# V-00735-01.net
KiCad netlist of a schematic drawn in EAGLE
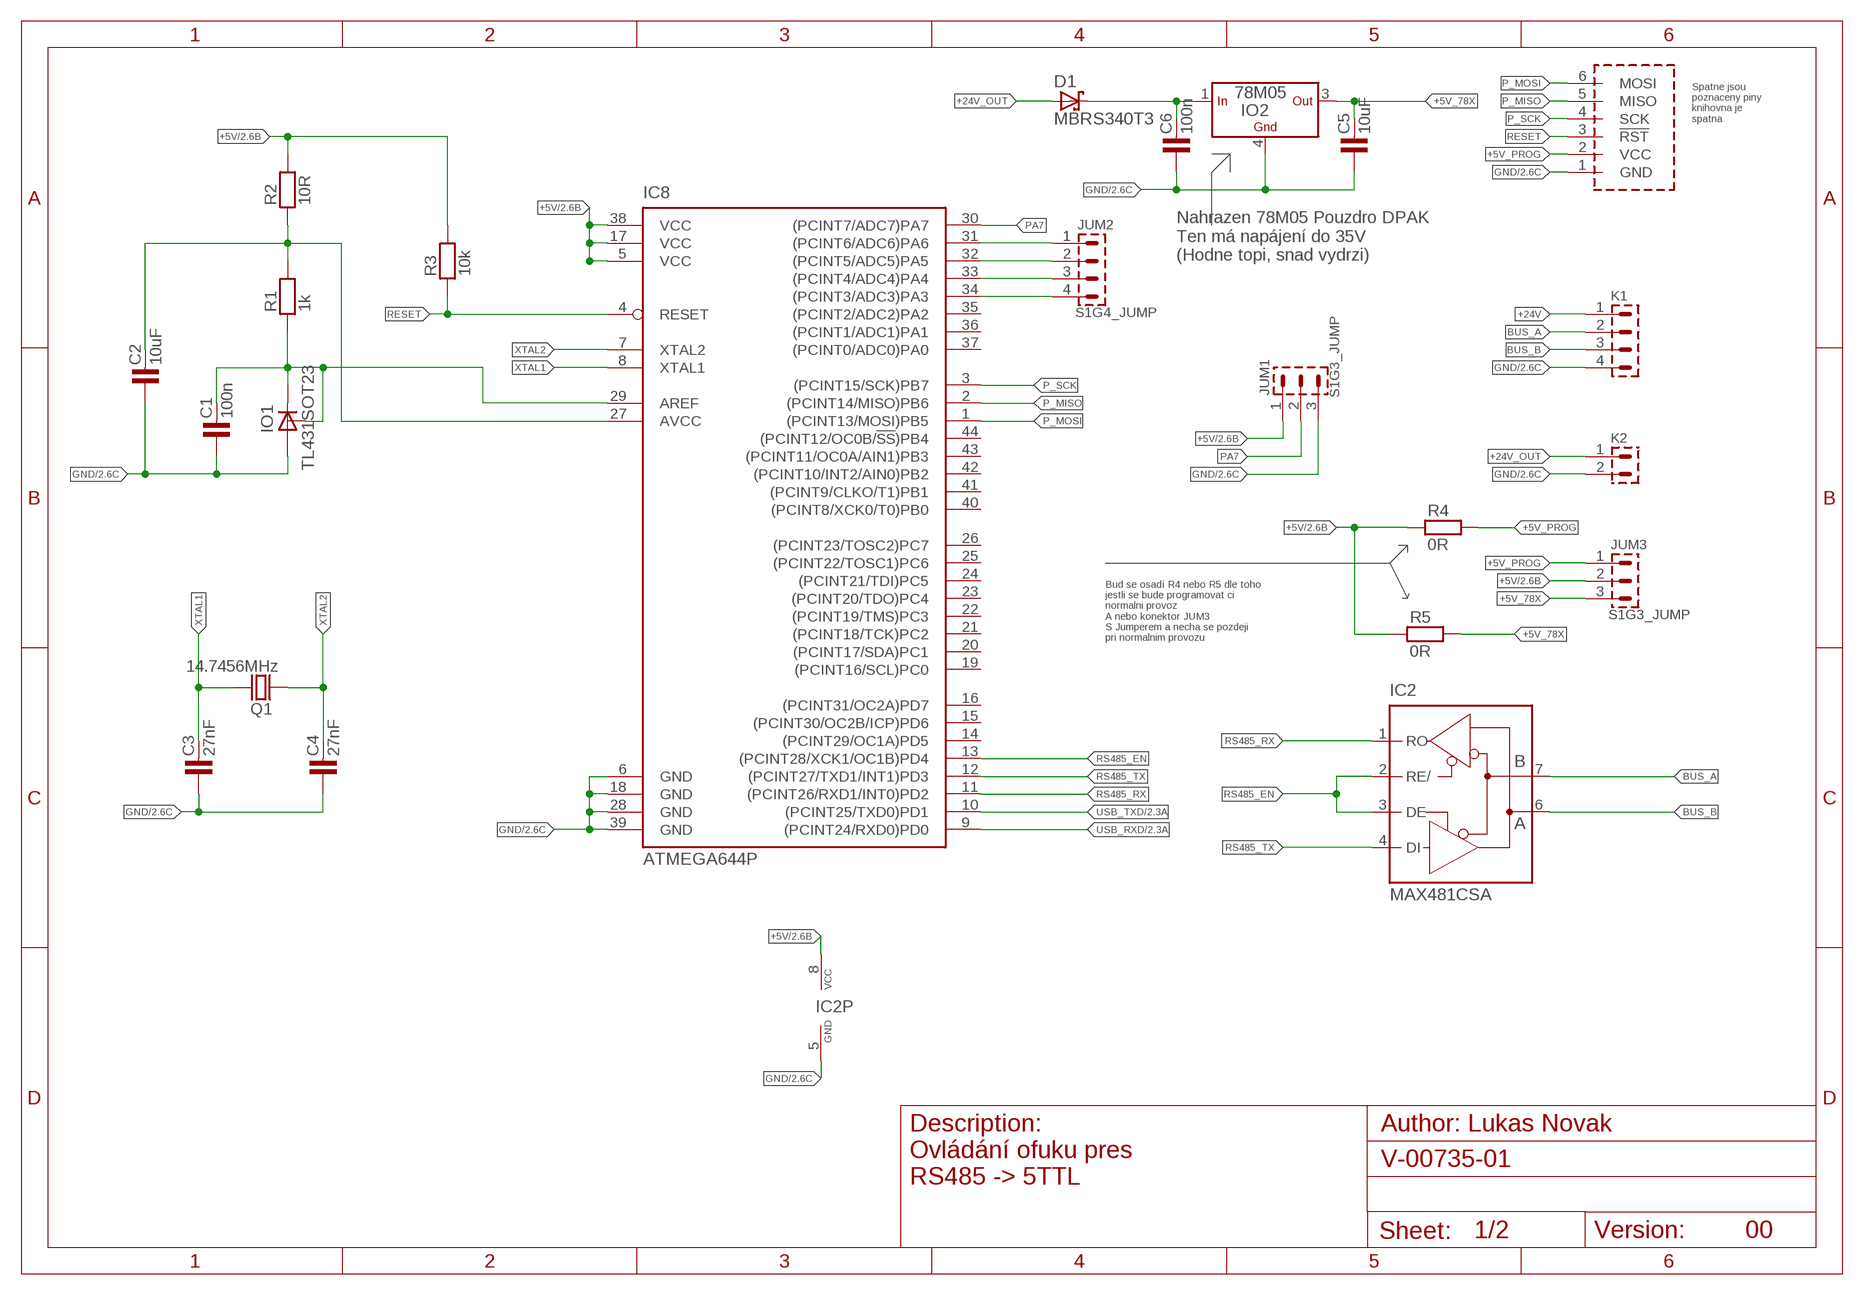
[diagram p0: schematic, sheet 1]
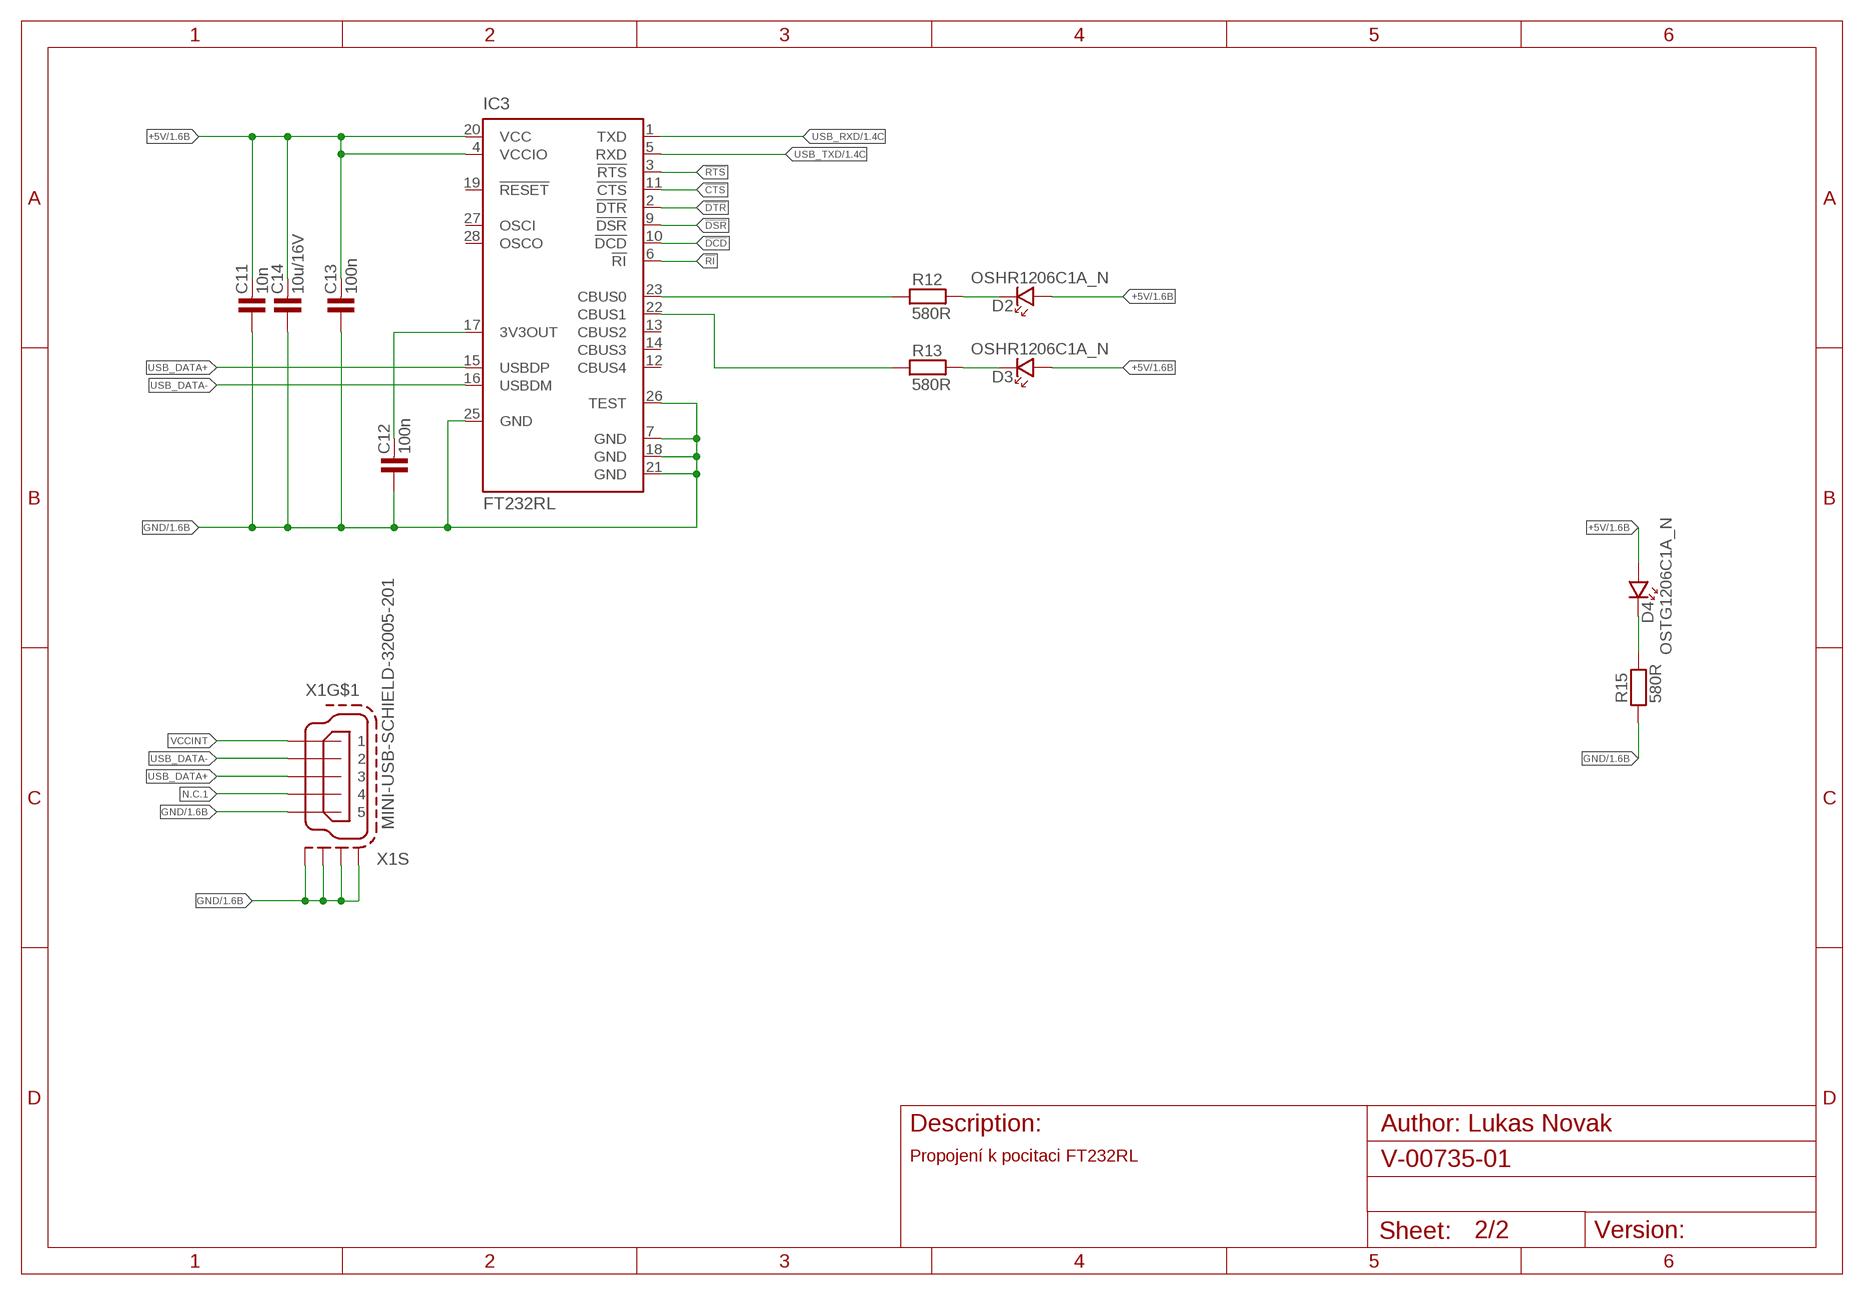
[diagram p1: schematic, sheet 2]

(export (version "E")
  (design (tool "Eeschema 10.0.6"))
  (components
    (comp (ref "C11")
      (value "10n")
      (footprint "eagle-import:1206")
      (libsource (lib "eagle-import") (part "C-KER_1206"))
    )
    (comp (ref "C12")
      (value "100n")
      (footprint "eagle-import:1206")
      (libsource (lib "eagle-import") (part "C-KER_1206"))
    )
    (comp (ref "C13")
      (value "100n")
      (footprint "eagle-import:1206")
      (libsource (lib "eagle-import") (part "C-KER_1206"))
    )
    (comp (ref "C14")
      (value "10u/16V")
      (footprint "eagle-import:1206")
      (libsource (lib "eagle-import") (part "C-KER_1206"))
    )
    (comp (ref "D2")
      (value "OSHR1206C1A_N")
      (footprint "eagle-import:P1206")
      (libsource (lib "eagle-import") (part "LED_1206"))
    )
    (comp (ref "D3")
      (value "OSHR1206C1A_N")
      (footprint "eagle-import:P1206")
      (libsource (lib "eagle-import") (part "LED_1206"))
    )
    (comp (ref "D4")
      (value "OSTG1206C1A_N")
      (footprint "eagle-import:P1206")
      (libsource (lib "eagle-import") (part "LED_1206"))
    )
    (comp (ref "IC3")
      (value "FT232RL")
      (footprint "eagle-import:SSOP28")
      (libsource (lib "eagle-import") (part "FT232RL"))
    )
    (comp (ref "R12")
      (value "580R")
      (footprint "eagle-import:1206")
      (libsource (lib "eagle-import") (part "R_1206"))
    )
    (comp (ref "R13")
      (value "580R")
      (footprint "eagle-import:1206")
      (libsource (lib "eagle-import") (part "R_1206"))
    )
    (comp (ref "R15")
      (value "580R")
      (footprint "eagle-import:1206")
      (libsource (lib "eagle-import") (part "R_1206"))
    )
    (comp (ref "X1")
      (value "MINI-USB-SCHIELD-32005-201")
      (footprint "eagle-import:32005-201")
      (libsource (lib "eagle-import") (part "MINI-USB-SCHIELD-32005-201"))
    )
    (comp (ref "C1")
      (value "100n")
      (footprint "eagle-import:1206")
      (libsource (lib "eagle-import") (part "C-KER_1206"))
    )
    (comp (ref "C2")
      (value "10uF")
      (footprint "eagle-import:1206")
      (libsource (lib "eagle-import") (part "C-KER_1206"))
    )
    (comp (ref "C3")
      (value "27nF")
      (footprint "eagle-import:0805")
      (libsource (lib "eagle-import") (part "C-KER_0805"))
    )
    (comp (ref "C4")
      (value "27nF")
      (footprint "eagle-import:0805")
      (libsource (lib "eagle-import") (part "C-KER_0805"))
    )
    (comp (ref "C5")
      (value "10uF")
      (footprint "eagle-import:1206")
      (libsource (lib "eagle-import") (part "C-KER_1206"))
    )
    (comp (ref "C6")
      (value "100n")
      (footprint "eagle-import:1206")
      (libsource (lib "eagle-import") (part "C-KER_1206"))
    )
    (comp (ref "D1")
      (value "MBRS340T3")
      (footprint "eagle-import:SMC")
      (libsource (lib "eagle-import") (part "MBRS30T34"))
    )
    (comp (ref "IC2")
      (value "MAX481CSA")
      (footprint "eagle-import:SO08")
      (fields (field (name "MF") "MAXIM"))
      (libsource (lib "eagle-import") (part "MAX481CSA"))
    )
    (comp (ref "IC8")
      (value "ATMEGA644P")
      (footprint "eagle-import:TQFP44")
      (libsource (lib "eagle-import") (part "ATMEGA644P"))
    )
    (comp (ref "IO1")
      (value "TL431SOT23")
      (footprint "eagle-import:SOT23")
      (fields (field (name "MPN") "TL431BFDT"))
      (libsource (lib "eagle-import") (part "TL431SOT23"))
    )
    (comp (ref "IO2")
      (value "78M05")
      (footprint "eagle-import:DPAK")
      (libsource (lib "eagle-import") (part "LF_CDT"))
    )
    (comp (ref "JUM1")
      (value "S1G3_JUMP")
      (footprint "eagle-import:S1G3_JUM")
      (libsource (lib "eagle-import") (part "S1G3_JUMP"))
    )
    (comp (ref "JUM2")
      (value "S1G4_JUMP")
      (footprint "eagle-import:S1G4_JUM")
      (libsource (lib "eagle-import") (part "S1G4_JUMP"))
    )
    (comp (ref "JUM3")
      (value "S1G3_JUMP")
      (footprint "eagle-import:S1G3_JUM")
      (libsource (lib "eagle-import") (part "S1G3_JUMP"))
    )
    (comp (ref "K1")
      (value "PSH02-04P")
      (footprint "eagle-import:PSH02-04P")
      (libsource (lib "eagle-import") (part "PSH02-04P"))
    )
    (comp (ref "K2")
      (value "PSH02-02P")
      (footprint "eagle-import:PSH02-02P")
      (libsource (lib "eagle-import") (part "PSH02-02P"))
    )
    (comp (ref "Q1")
      (value "14.7456MHz")
      (footprint "eagle-import:HC-49U")
      (libsource (lib "eagle-import") (part "Q_HC-49U"))
    )
    (comp (ref "R1")
      (value "1k")
      (footprint "eagle-import:1206")
      (libsource (lib "eagle-import") (part "R_1206"))
    )
    (comp (ref "R2")
      (value "10R")
      (footprint "eagle-import:1206")
      (libsource (lib "eagle-import") (part "R_1206"))
    )
    (comp (ref "R3")
      (value "10k")
      (footprint "eagle-import:1206")
      (libsource (lib "eagle-import") (part "R_1206"))
    )
    (comp (ref "R4")
      (value "0R")
      (footprint "eagle-import:1206")
      (libsource (lib "eagle-import") (part "R_1206"))
    )
    (comp (ref "R5")
      (value "0R")
      (footprint "eagle-import:1206")
      (libsource (lib "eagle-import") (part "R_1206"))
    )
    (comp (ref "U$1")
      (value "AVR_PROG_SPI")
      (footprint "eagle-import:PSH02-06P")
      (libsource (lib "eagle-import") (part "AVR_PROG_SPI"))
    )
  )
  (nets
    (net (code "1") (name "+5V") (class "Default")
      (node (ref "C11") (pin "2") (pinfunction "2_2") (pintype "passive"))
      (node (ref "C13") (pin "2") (pinfunction "2_2") (pintype "passive"))
      (node (ref "C14") (pin "2") (pinfunction "2_2") (pintype "passive"))
      (node (ref "D2") (pin "A") (pinfunction "A_A") (pintype "passive"))
      (node (ref "D3") (pin "A") (pinfunction "A_A") (pintype "passive"))
      (node (ref "D4") (pin "A") (pinfunction "A_A") (pintype "passive"))
      (node (ref "IC2") (pin "8") (pinfunction "VCC_8") (pintype "power_in"))
      (node (ref "IC3") (pin "20") (pinfunction "VCC_20") (pintype "power_in"))
      (node (ref "IC3") (pin "4") (pinfunction "VCCIO_4") (pintype "power_in"))
      (node (ref "IC8") (pin "17") (pinfunction "VCC_17") (pintype "power_in"))
      (node (ref "IC8") (pin "38") (pinfunction "VCC_38") (pintype "power_in"))
      (node (ref "IC8") (pin "5") (pinfunction "VCC_5") (pintype "power_in"))
      (node (ref "JUM1") (pin "1") (pinfunction "1_1") (pintype "passive"))
      (node (ref "JUM3") (pin "2") (pinfunction "2_2") (pintype "passive"))
      (node (ref "R2") (pin "2") (pinfunction "2_2") (pintype "passive"))
      (node (ref "R3") (pin "2") (pinfunction "2_2") (pintype "passive"))
      (node (ref "R4") (pin "1") (pinfunction "1_1") (pintype "passive"))
      (node (ref "R5") (pin "1") (pinfunction "1_1") (pintype "passive"))
    )
    (net (code "2") (name "+5V_78X") (class "Default")
      (node (ref "C5") (pin "2") (pinfunction "2_2") (pintype "passive"))
      (node (ref "IO2") (pin "3") (pinfunction "OUT_3") (pintype "passive"))
      (node (ref "JUM3") (pin "3") (pinfunction "3_3") (pintype "passive"))
      (node (ref "R5") (pin "2") (pinfunction "2_2") (pintype "passive"))
    )
    (net (code "3") (name "+5V_PROG") (class "Default")
      (node (ref "JUM3") (pin "1") (pinfunction "1_1") (pintype "passive"))
      (node (ref "R4") (pin "2") (pinfunction "2_2") (pintype "passive"))
      (node (ref "U$1") (pin "2") (pinfunction "VCC_2") (pintype "bidirectional"))
    )
    (net (code "4") (name "+24V") (class "Default")
      (node (ref "C6") (pin "2") (pinfunction "2_2") (pintype "passive"))
      (node (ref "D1") (pin "C") (pinfunction "C_C") (pintype "passive"))
      (node (ref "IO2") (pin "1") (pinfunction "IN_1") (pintype "passive"))
      (node (ref "K1") (pin "1") (pinfunction "1_1") (pintype "passive"))
    )
    (net (code "5") (name "+24V_OUT") (class "Default")
      (node (ref "D1") (pin "A") (pinfunction "A_A") (pintype "passive"))
      (node (ref "K2") (pin "1") (pinfunction "1_1") (pintype "passive"))
    )
    (net (code "6") (name "BUS_A") (class "Default")
      (node (ref "IC2") (pin "7") (pinfunction "B_7") (pintype "passive"))
      (node (ref "K1") (pin "2") (pinfunction "2_2") (pintype "passive"))
    )
    (net (code "7") (name "BUS_B") (class "Default")
      (node (ref "IC2") (pin "6") (pinfunction "A_6") (pintype "passive"))
      (node (ref "K1") (pin "3") (pinfunction "3_3") (pintype "passive"))
    )
    (net (code "8") (name "GND") (class "Default")
      (node (ref "C1") (pin "1") (pinfunction "1_1") (pintype "passive"))
      (node (ref "C11") (pin "1") (pinfunction "1_1") (pintype "passive"))
      (node (ref "C12") (pin "1") (pinfunction "1_1") (pintype "passive"))
      (node (ref "C13") (pin "1") (pinfunction "1_1") (pintype "passive"))
      (node (ref "C14") (pin "1") (pinfunction "1_1") (pintype "passive"))
      (node (ref "C2") (pin "1") (pinfunction "1_1") (pintype "passive"))
      (node (ref "C3") (pin "1") (pinfunction "1_1") (pintype "passive"))
      (node (ref "C4") (pin "1") (pinfunction "1_1") (pintype "passive"))
      (node (ref "C5") (pin "1") (pinfunction "1_1") (pintype "passive"))
      (node (ref "C6") (pin "1") (pinfunction "1_1") (pintype "passive"))
      (node (ref "IC2") (pin "5") (pinfunction "GND_5") (pintype "power_in"))
      (node (ref "IC3") (pin "18") (pinfunction "GND_18") (pintype "power_in"))
      (node (ref "IC3") (pin "21") (pinfunction "GND_21") (pintype "power_in"))
      (node (ref "IC3") (pin "25") (pinfunction "GND_25") (pintype "power_in"))
      (node (ref "IC3") (pin "26") (pinfunction "TEST_26") (pintype "input"))
      (node (ref "IC3") (pin "7") (pinfunction "GND_7") (pintype "power_in"))
      (node (ref "IC8") (pin "18") (pinfunction "GND_18") (pintype "power_in"))
      (node (ref "IC8") (pin "28") (pinfunction "GND_28") (pintype "power_in"))
      (node (ref "IC8") (pin "39") (pinfunction "GND_39") (pintype "power_in"))
      (node (ref "IC8") (pin "6") (pinfunction "GND_6") (pintype "power_in"))
      (node (ref "IO1") (pin "3") (pinfunction "A_3") (pintype "bidirectional"))
      (node (ref "IO2") (pin "4") (pinfunction "GND_4") (pintype "passive"))
      (node (ref "JUM1") (pin "3") (pinfunction "3_3") (pintype "passive"))
      (node (ref "K1") (pin "4") (pinfunction "4_4") (pintype "passive"))
      (node (ref "K2") (pin "2") (pinfunction "2_2") (pintype "passive"))
      (node (ref "R15") (pin "1") (pinfunction "1_1") (pintype "passive"))
      (node (ref "U$1") (pin "1") (pinfunction "GND_1") (pintype "bidirectional"))
      (node (ref "X1") (pin "5") (pinfunction "5_5") (pintype "passive"))
      (node (ref "X1") (pin "M1") (pinfunction "S1_M1") (pintype "passive"))
      (node (ref "X1") (pin "M2") (pinfunction "S2_M2") (pintype "passive"))
      (node (ref "X1") (pin "M3") (pinfunction "S3_M3") (pintype "passive"))
      (node (ref "X1") (pin "M4") (pinfunction "S4_M4") (pintype "passive"))
    )
    (net (code "9") (name "N.C.1") (class "Default")
      (node (ref "X1") (pin "4") (pinfunction "4_4") (pintype "passive"))
    )
    (net (code "10") (name "Net-(D2-PadK)") (class "Default")
      (node (ref "D2") (pin "K") (pinfunction "K_K") (pintype "passive"))
      (node (ref "R12") (pin "2") (pinfunction "2_2") (pintype "passive"))
    )
    (net (code "11") (name "Net-(D3-PadK)") (class "Default")
      (node (ref "D3") (pin "K") (pinfunction "K_K") (pintype "passive"))
      (node (ref "R13") (pin "2") (pinfunction "2_2") (pintype "passive"))
    )
    (net (code "12") (name "Net-(D4-PadK)") (class "Default")
      (node (ref "D4") (pin "K") (pinfunction "K_K") (pintype "passive"))
      (node (ref "R15") (pin "2") (pinfunction "2_2") (pintype "passive"))
    )
    (net (code "13") (name "Net-(IC3-3V3OUT)") (class "Default")
      (node (ref "C12") (pin "2") (pinfunction "2_2") (pintype "passive"))
      (node (ref "IC3") (pin "17") (pinfunction "3V3OUT_17") (pintype "output"))
    )
    (net (code "14") (name "Net-(IC3-CBUS0)") (class "Default")
      (node (ref "IC3") (pin "23") (pinfunction "CBUS0_23") (pintype "bidirectional"))
      (node (ref "R12") (pin "1") (pinfunction "1_1") (pintype "passive"))
    )
    (net (code "15") (name "Net-(IC3-CBUS1)") (class "Default")
      (node (ref "IC3") (pin "22") (pinfunction "CBUS1_22") (pintype "bidirectional"))
      (node (ref "R13") (pin "1") (pinfunction "1_1") (pintype "passive"))
    )
    (net (code "16") (name "Net-(IC8-(PCINT3{slash}ADC3)PA3)") (class "Default")
      (node (ref "IC8") (pin "34") (pinfunction "(PCINT3/ADC3)PA3_34") (pintype "bidirectional"))
      (node (ref "JUM2") (pin "4") (pinfunction "4_4") (pintype "passive"))
    )
    (net (code "17") (name "Net-(IC8-(PCINT4{slash}ADC4)PA4)") (class "Default")
      (node (ref "IC8") (pin "33") (pinfunction "(PCINT4/ADC4)PA4_33") (pintype "bidirectional"))
      (node (ref "JUM2") (pin "3") (pinfunction "3_3") (pintype "passive"))
    )
    (net (code "18") (name "Net-(IC8-(PCINT5{slash}ADC5)PA5)") (class "Default")
      (node (ref "IC8") (pin "32") (pinfunction "(PCINT5/ADC5)PA5_32") (pintype "bidirectional"))
      (node (ref "JUM2") (pin "2") (pinfunction "2_2") (pintype "passive"))
    )
    (net (code "19") (name "Net-(IC8-(PCINT6{slash}ADC6)PA6)") (class "Default")
      (node (ref "IC8") (pin "31") (pinfunction "(PCINT6/ADC6)PA6_31") (pintype "bidirectional"))
      (node (ref "JUM2") (pin "1") (pinfunction "1_1") (pintype "passive"))
    )
    (net (code "20") (name "Net-(IC8-AREF)") (class "Default")
      (node (ref "C1") (pin "2") (pinfunction "2_2") (pintype "passive"))
      (node (ref "IC8") (pin "29") (pinfunction "AREF_29") (pintype "passive"))
      (node (ref "IO1") (pin "1") (pinfunction "C_1") (pintype "bidirectional"))
      (node (ref "IO1") (pin "2") (pinfunction "R_2") (pintype "bidirectional"))
      (node (ref "R1") (pin "1") (pinfunction "1_1") (pintype "passive"))
    )
    (net (code "21") (name "Net-(IC8-AVCC)") (class "Default")
      (node (ref "C2") (pin "2") (pinfunction "2_2") (pintype "passive"))
      (node (ref "IC8") (pin "27") (pinfunction "AVCC_27") (pintype "power_in"))
      (node (ref "R1") (pin "2") (pinfunction "2_2") (pintype "passive"))
      (node (ref "R2") (pin "1") (pinfunction "1_1") (pintype "passive"))
    )
    (net (code "22") (name "PA7") (class "Default")
      (node (ref "IC8") (pin "30") (pinfunction "(PCINT7/ADC7)PA7_30") (pintype "bidirectional"))
      (node (ref "JUM1") (pin "2") (pinfunction "2_2") (pintype "passive"))
    )
    (net (code "23") (name "P_MISO") (class "Default")
      (node (ref "IC8") (pin "2") (pinfunction "(PCINT14/MISO)PB6_2") (pintype "bidirectional"))
      (node (ref "U$1") (pin "5") (pinfunction "MISO_5") (pintype "bidirectional"))
    )
    (net (code "24") (name "P_MOSI") (class "Default")
      (node (ref "IC8") (pin "1") (pinfunction "(PCINT13/MOSI)PB5_1") (pintype "bidirectional"))
      (node (ref "U$1") (pin "6") (pinfunction "MOSI_6") (pintype "bidirectional"))
    )
    (net (code "25") (name "P_SCK") (class "Default")
      (node (ref "IC8") (pin "3") (pinfunction "(PCINT15/SCK)PB7_3") (pintype "bidirectional"))
      (node (ref "U$1") (pin "4") (pinfunction "SCK_4") (pintype "bidirectional"))
    )
    (net (code "26") (name "RESET") (class "Default")
      (node (ref "IC8") (pin "4") (pinfunction "RESET_4") (pintype "input"))
      (node (ref "R3") (pin "1") (pinfunction "1_1") (pintype "passive"))
      (node (ref "U$1") (pin "3") (pinfunction "~{RST}_3") (pintype "bidirectional"))
    )
    (net (code "27") (name "RS485_EN") (class "Default")
      (node (ref "IC2") (pin "2") (pinfunction "RE/_2") (pintype "input"))
      (node (ref "IC2") (pin "3") (pinfunction "DE_3") (pintype "input"))
      (node (ref "IC8") (pin "13") (pinfunction "(PCINT28/XCK1/OC1B)PD4_13") (pintype "bidirectional"))
    )
    (net (code "28") (name "RS485_RX") (class "Default")
      (node (ref "IC2") (pin "1") (pinfunction "RO_1") (pintype "output"))
      (node (ref "IC8") (pin "11") (pinfunction "(PCINT26/RXD1/INT0)PD2_11") (pintype "bidirectional"))
    )
    (net (code "29") (name "RS485_TX") (class "Default")
      (node (ref "IC2") (pin "4") (pinfunction "DI_4") (pintype "input"))
      (node (ref "IC8") (pin "12") (pinfunction "(PCINT27/TXD1/INT1)PD3_12") (pintype "bidirectional"))
    )
    (net (code "30") (name "USB_DATA+") (class "Default")
      (node (ref "IC3") (pin "15") (pinfunction "USBDP_15") (pintype "bidirectional"))
      (node (ref "X1") (pin "3") (pinfunction "3_3") (pintype "passive"))
    )
    (net (code "31") (name "USB_DATA-") (class "Default")
      (node (ref "IC3") (pin "16") (pinfunction "USBDM_16") (pintype "bidirectional"))
      (node (ref "X1") (pin "2") (pinfunction "2_2") (pintype "passive"))
    )
    (net (code "32") (name "USB_RXD") (class "Default")
      (node (ref "IC3") (pin "1") (pinfunction "TXD_1") (pintype "output"))
      (node (ref "IC8") (pin "9") (pinfunction "(PCINT24/RXD0)PD0_9") (pintype "bidirectional"))
    )
    (net (code "33") (name "USB_TXD") (class "Default")
      (node (ref "IC3") (pin "5") (pinfunction "RXD_5") (pintype "input"))
      (node (ref "IC8") (pin "10") (pinfunction "(PCINT25/TXD0)PD1_10") (pintype "bidirectional"))
    )
    (net (code "34") (name "VCCINT") (class "Default")
      (node (ref "X1") (pin "1") (pinfunction "1_1") (pintype "passive"))
    )
    (net (code "35") (name "XTAL1") (class "Default")
      (node (ref "C3") (pin "2") (pinfunction "2_2") (pintype "passive"))
      (node (ref "IC8") (pin "8") (pinfunction "XTAL1_8") (pintype "bidirectional"))
      (node (ref "Q1") (pin "2") (pinfunction "2_2") (pintype "passive"))
    )
    (net (code "36") (name "XTAL2") (class "Default")
      (node (ref "C4") (pin "2") (pinfunction "2_2") (pintype "passive"))
      (node (ref "IC8") (pin "7") (pinfunction "XTAL2_7") (pintype "bidirectional"))
      (node (ref "Q1") (pin "1") (pinfunction "1_1") (pintype "passive"))
    )
    (net (code "37") (name "unconnected-(IC3-CBUS2-Pad13)") (class "Default")
      (node (ref "IC3") (pin "13") (pinfunction "CBUS2_13") (pintype "bidirectional"))
    )
    (net (code "38") (name "unconnected-(IC3-CBUS3-Pad14)") (class "Default")
      (node (ref "IC3") (pin "14") (pinfunction "CBUS3_14") (pintype "bidirectional"))
    )
    (net (code "39") (name "unconnected-(IC3-CBUS4-Pad12)") (class "Default")
      (node (ref "IC3") (pin "12") (pinfunction "CBUS4_12") (pintype "bidirectional"))
    )
    (net (code "40") (name "unconnected-(IC3-OSCI-Pad27)") (class "Default")
      (node (ref "IC3") (pin "27") (pinfunction "OSCI_27") (pintype "input"))
    )
    (net (code "41") (name "unconnected-(IC3-OSCO-Pad28)") (class "Default")
      (node (ref "IC3") (pin "28") (pinfunction "OSCO_28") (pintype "output"))
    )
    (net (code "42") (name "unconnected-(IC3-~{RESET}-Pad19)") (class "Default")
      (node (ref "IC3") (pin "19") (pinfunction "~{RESET}_19") (pintype "input"))
    )
    (net (code "43") (name "unconnected-(IC8-(PCINT0{slash}ADC0)PA0-Pad37)") (class "Default")
      (node (ref "IC8") (pin "37") (pinfunction "(PCINT0/ADC0)PA0_37") (pintype "bidirectional"))
    )
    (net (code "44") (name "unconnected-(IC8-(PCINT1{slash}ADC1)PA1-Pad36)") (class "Default")
      (node (ref "IC8") (pin "36") (pinfunction "(PCINT1/ADC1)PA1_36") (pintype "bidirectional"))
    )
    (net (code "45") (name "unconnected-(IC8-(PCINT2{slash}ADC2)PA2-Pad35)") (class "Default")
      (node (ref "IC8") (pin "35") (pinfunction "(PCINT2/ADC2)PA2_35") (pintype "bidirectional"))
    )
    (net (code "46") (name "unconnected-(IC8-(PCINT8{slash}XCK0{slash}T0)PB0-Pad40)") (class "Default")
      (node (ref "IC8") (pin "40") (pinfunction "(PCINT8/XCK0/T0)PB0_40") (pintype "bidirectional"))
    )
    (net (code "47") (name "unconnected-(IC8-(PCINT9{slash}CLKO{slash}T1)PB1-Pad41)") (class "Default")
      (node (ref "IC8") (pin "41") (pinfunction "(PCINT9/CLKO/T1)PB1_41") (pintype "bidirectional"))
    )
    (net (code "48") (name "unconnected-(IC8-(PCINT10{slash}INT2{slash}AIN0)PB2-Pad42)") (class "Default")
      (node (ref "IC8") (pin "42") (pinfunction "(PCINT10/INT2/AIN0)PB2_42") (pintype "bidirectional"))
    )
    (net (code "49") (name "unconnected-(IC8-(PCINT11{slash}OC0A{slash}AIN1)PB3-Pad43)") (class "Default")
      (node (ref "IC8") (pin "43") (pinfunction "(PCINT11/OC0A/AIN1)PB3_43") (pintype "bidirectional"))
    )
    (net (code "50") (name "unconnected-(IC8-(PCINT12{slash}OC0B{slash}~{SS})PB4-Pad44)") (class "Default")
      (node (ref "IC8") (pin "44") (pinfunction "(PCINT12/OC0B/~{SS})PB4_44") (pintype "bidirectional"))
    )
    (net (code "51") (name "unconnected-(IC8-(PCINT16{slash}SCL)PC0-Pad19)") (class "Default")
      (node (ref "IC8") (pin "19") (pinfunction "(PCINT16/SCL)PC0_19") (pintype "output"))
    )
    (net (code "52") (name "unconnected-(IC8-(PCINT17{slash}SDA)PC1-Pad20)") (class "Default")
      (node (ref "IC8") (pin "20") (pinfunction "(PCINT17/SDA)PC1_20") (pintype "output"))
    )
    (net (code "53") (name "unconnected-(IC8-(PCINT18{slash}TCK)PC2-Pad21)") (class "Default")
      (node (ref "IC8") (pin "21") (pinfunction "(PCINT18/TCK)PC2_21") (pintype "output"))
    )
    (net (code "54") (name "unconnected-(IC8-(PCINT19{slash}TMS)PC3-Pad22)") (class "Default")
      (node (ref "IC8") (pin "22") (pinfunction "(PCINT19/TMS)PC3_22") (pintype "output"))
    )
    (net (code "55") (name "unconnected-(IC8-(PCINT20{slash}TDO)PC4-Pad23)") (class "Default")
      (node (ref "IC8") (pin "23") (pinfunction "(PCINT20/TDO)PC4_23") (pintype "output"))
    )
    (net (code "56") (name "unconnected-(IC8-(PCINT21{slash}TDI)PC5-Pad24)") (class "Default")
      (node (ref "IC8") (pin "24") (pinfunction "(PCINT21/TDI)PC5_24") (pintype "output"))
    )
    (net (code "57") (name "unconnected-(IC8-(PCINT22{slash}TOSC1)PC6-Pad25)") (class "Default")
      (node (ref "IC8") (pin "25") (pinfunction "(PCINT22/TOSC1)PC6_25") (pintype "output"))
    )
    (net (code "58") (name "unconnected-(IC8-(PCINT23{slash}TOSC2)PC7-Pad26)") (class "Default")
      (node (ref "IC8") (pin "26") (pinfunction "(PCINT23/TOSC2)PC7_26") (pintype "output"))
    )
    (net (code "59") (name "unconnected-(IC8-(PCINT29{slash}OC1A)PD5-Pad14)") (class "Default")
      (node (ref "IC8") (pin "14") (pinfunction "(PCINT29/OC1A)PD5_14") (pintype "bidirectional"))
    )
    (net (code "60") (name "unconnected-(IC8-(PCINT30{slash}OC2B{slash}ICP)PD6-Pad15)") (class "Default")
      (node (ref "IC8") (pin "15") (pinfunction "(PCINT30/OC2B/ICP)PD6_15") (pintype "bidirectional"))
    )
    (net (code "61") (name "unconnected-(IC8-(PCINT31{slash}OC2A)PD7-Pad16)") (class "Default")
      (node (ref "IC8") (pin "16") (pinfunction "(PCINT31/OC2A)PD7_16") (pintype "bidirectional"))
    )
    (net (code "62") (name "~{CTS}") (class "Default")
      (node (ref "IC3") (pin "11") (pinfunction "~{CTS}_11") (pintype "input"))
    )
    (net (code "63") (name "~{DCD}") (class "Default")
      (node (ref "IC3") (pin "10") (pinfunction "~{DCD}_10") (pintype "input"))
    )
    (net (code "64") (name "~{DSR}") (class "Default")
      (node (ref "IC3") (pin "9") (pinfunction "~{DSR}_9") (pintype "input"))
    )
    (net (code "65") (name "~{DTR}") (class "Default")
      (node (ref "IC3") (pin "2") (pinfunction "~{DTR}_2") (pintype "output"))
    )
    (net (code "66") (name "~{RI}") (class "Default")
      (node (ref "IC3") (pin "6") (pinfunction "~{RI}_6") (pintype "input"))
    )
    (net (code "67") (name "~{RTS}") (class "Default")
      (node (ref "IC3") (pin "3") (pinfunction "~{RTS}_3") (pintype "output"))
    )
  )
)
